# PCA9306DP1.net
KiCad netlist of a schematic drawn in Altium Designer
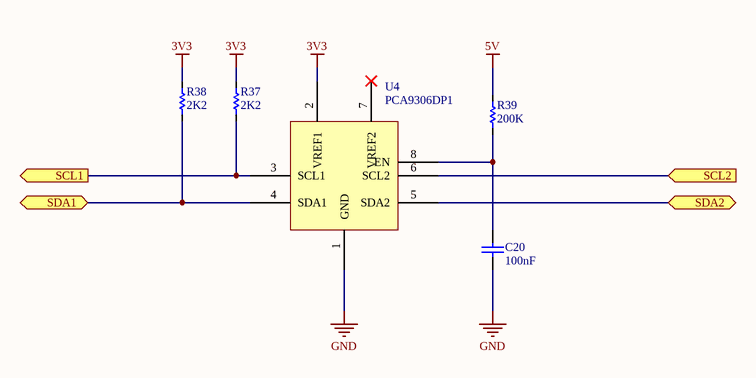
[diagram p0: PCA9306DP1.SchDoc]

(export (version "E")
  (design (tool "Eeschema 10.0.6"))
  (components
    (comp (ref "C20")
      (value "100nF")
      (footprint "C0603(1608)")
      (description "Capacitor")
      (libsource (lib "Miscellaneous Devices") (part "Cap"))
    )
    (comp (ref "R37")
      (value "2K2")
      (footprint "R0603(1608)")
      (description "Resistor")
      (libsource (lib "ali_lib") (part "R"))
    )
    (comp (ref "R38")
      (value "2K2")
      (footprint "R0603(1608)")
      (description "Resistor")
      (libsource (lib "ali_lib") (part "R"))
    )
    (comp (ref "R39")
      (value "200K")
      (footprint "R0603(1608)")
      (description "Resistor")
      (libsource (lib "ali_lib") (part "R"))
    )
    (comp (ref "U4")
      (value "PCA9306DP1")
      (footprint "8-TSSOP")
      (description "Dual bidirectional I2C-bus and SMBus voltage-level translator")
      (fields
        (field (name "MANUFACTURER") "NXP Semiconductors")
        (field (name "MANUFACTURER PART NUMBER") "PCA9306DP1,125")
      )
      (libsource (lib "Flight_Controller") (part "PCA9306DP1"))
    )
  )
  (nets
    (net (code "1") (name "/SCL1") (class "Default")
      (node (ref "R37") (pin "1") (pinfunction "1_1") (pintype "passive"))
      (node (ref "U4") (pin "3") (pinfunction "SCL1_3") (pintype "passive"))
    )
    (net (code "2") (name "/SCL2") (class "Default")
      (node (ref "U4") (pin "6") (pinfunction "SCL2_6") (pintype "passive"))
    )
    (net (code "3") (name "/SDA1") (class "Default")
      (node (ref "R38") (pin "1") (pinfunction "1_1") (pintype "passive"))
      (node (ref "U4") (pin "4") (pinfunction "SDA1_4") (pintype "passive"))
    )
    (net (code "4") (name "/SDA2") (class "Default")
      (node (ref "U4") (pin "5") (pinfunction "SDA2_5") (pintype "passive"))
    )
    (net (code "5") (name "3V3") (class "Default")
      (node (ref "R37") (pin "2") (pinfunction "2_2") (pintype "passive"))
      (node (ref "R38") (pin "2") (pinfunction "2_2") (pintype "passive"))
      (node (ref "U4") (pin "2") (pinfunction "VREF1_2") (pintype "passive"))
    )
    (net (code "6") (name "5V") (class "Default")
      (node (ref "R39") (pin "2") (pinfunction "2_2") (pintype "passive"))
    )
    (net (code "7") (name "GND") (class "Default")
      (node (ref "C20") (pin "1") (pinfunction "1_1") (pintype "passive"))
      (node (ref "U4") (pin "1") (pinfunction "GND_1") (pintype "passive"))
    )
    (net (code "8") (name "Net-(U4-EN)") (class "Default")
      (node (ref "C20") (pin "2") (pinfunction "2_2") (pintype "passive"))
      (node (ref "R39") (pin "1") (pinfunction "1_1") (pintype "passive"))
      (node (ref "U4") (pin "8") (pinfunction "EN_8") (pintype "passive"))
    )
    (net (code "9") (name "unconnected-(U4-VREF2-Pad7)") (class "Default")
      (node (ref "U4") (pin "7") (pinfunction "VREF2_7") (pintype "passive+no_connect"))
    )
  )
)
